# Temperature_Sensor_Rev_1.net
KiCad netlist of a schematic drawn in EAGLE
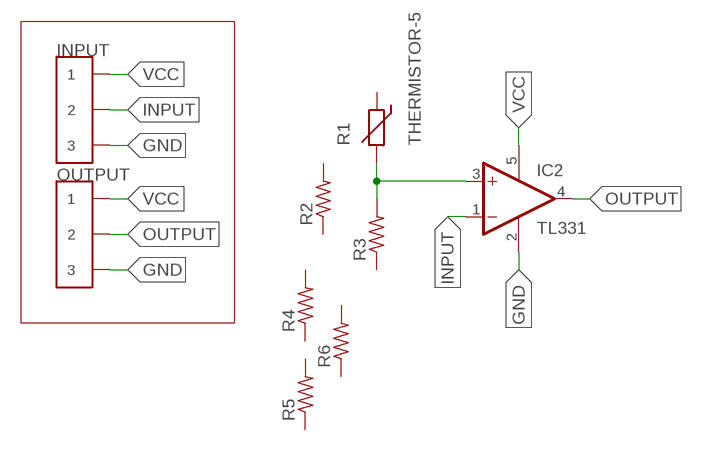
[diagram p0: schematic, sheet 1]

(export (version "E")
  (design (tool "Eeschema 10.0.6"))
  (components
    (comp (ref "IC2")
      (value "TL331")
      (footprint "eagle-import:DBV-R-PDSO-G5")
      (libsource (lib "eagle-import") (part "TL331"))
    )
    (comp (ref "INPUT")
      (value "CONN_3")
      (footprint "eagle-import:CONNECTOR_3")
      (libsource (lib "eagle-import") (part "CONN_3"))
    )
    (comp (ref "OUTPUT")
      (value "CONN_3")
      (footprint "eagle-import:CONNECTOR_3")
      (libsource (lib "eagle-import") (part "CONN_3"))
    )
    (comp (ref "R1")
      (value "THERMISTOR-5")
      (footprint "eagle-import:R-5")
      (libsource (lib "eagle-import") (part "THERMISTOR-5"))
    )
    (comp (ref "R2")
      (value "R-US_R0805")
      (footprint "eagle-import:R0805")
      (libsource (lib "eagle-import") (part "R-US_R0805"))
    )
    (comp (ref "R3")
      (value "R-US_R0805")
      (footprint "eagle-import:R0805")
      (libsource (lib "eagle-import") (part "R-US_R0805"))
    )
    (comp (ref "R4")
      (value "R-US_R0805")
      (footprint "eagle-import:R0805")
      (libsource (lib "eagle-import") (part "R-US_R0805"))
    )
    (comp (ref "R5")
      (value "R-US_R0805")
      (footprint "eagle-import:R0805")
      (libsource (lib "eagle-import") (part "R-US_R0805"))
    )
    (comp (ref "R6")
      (value "R-US_R0805")
      (footprint "eagle-import:R0805")
      (libsource (lib "eagle-import") (part "R-US_R0805"))
    )
  )
  (nets
    (net (code "1") (name "GND") (class "Default")
      (node (ref "IC2") (pin "2") (pinfunction "GND_2") (pintype "power_in"))
      (node (ref "INPUT") (pin "5") (pinfunction "3_5") (pintype "bidirectional"))
      (node (ref "INPUT") (pin "6") (pinfunction "3_6") (pintype "bidirectional"))
      (node (ref "OUTPUT") (pin "5") (pinfunction "3_5") (pintype "bidirectional"))
      (node (ref "OUTPUT") (pin "6") (pinfunction "3_6") (pintype "bidirectional"))
    )
    (net (code "2") (name "INPUT") (class "Default")
      (node (ref "IC2") (pin "1") (pinfunction "-IN_1") (pintype "input"))
      (node (ref "INPUT") (pin "3") (pinfunction "2_3") (pintype "bidirectional"))
      (node (ref "INPUT") (pin "4") (pinfunction "2_4") (pintype "bidirectional"))
    )
    (net (code "3") (name "Net-(IC2-+IN)") (class "Default")
      (node (ref "IC2") (pin "3") (pinfunction "+IN_3") (pintype "input"))
      (node (ref "R1") (pin "2") (pinfunction "2_2") (pintype "passive"))
      (node (ref "R3") (pin "2") (pinfunction "2_2") (pintype "passive"))
    )
    (net (code "4") (name "OUTPUT") (class "Default")
      (node (ref "IC2") (pin "4") (pinfunction "OUT_4") (pintype "output"))
      (node (ref "OUTPUT") (pin "3") (pinfunction "2_3") (pintype "bidirectional"))
      (node (ref "OUTPUT") (pin "4") (pinfunction "2_4") (pintype "bidirectional"))
    )
    (net (code "5") (name "VCC") (class "Default")
      (node (ref "IC2") (pin "5") (pinfunction "V+_5") (pintype "power_in"))
      (node (ref "INPUT") (pin "1") (pinfunction "1_1") (pintype "bidirectional"))
      (node (ref "INPUT") (pin "2") (pinfunction "1_2") (pintype "bidirectional"))
      (node (ref "OUTPUT") (pin "1") (pinfunction "1_1") (pintype "bidirectional"))
      (node (ref "OUTPUT") (pin "2") (pinfunction "1_2") (pintype "bidirectional"))
    )
    (net (code "6") (name "unconnected-(R1-Pad1)") (class "Default")
      (node (ref "R1") (pin "1") (pinfunction "1_1") (pintype "passive"))
    )
    (net (code "7") (name "unconnected-(R2-Pad1)") (class "Default")
      (node (ref "R2") (pin "1") (pinfunction "1_1") (pintype "passive"))
    )
    (net (code "8") (name "unconnected-(R2-Pad2)") (class "Default")
      (node (ref "R2") (pin "2") (pinfunction "2_2") (pintype "passive"))
    )
    (net (code "9") (name "unconnected-(R3-Pad1)") (class "Default")
      (node (ref "R3") (pin "1") (pinfunction "1_1") (pintype "passive"))
    )
    (net (code "10") (name "unconnected-(R4-Pad1)") (class "Default")
      (node (ref "R4") (pin "1") (pinfunction "1_1") (pintype "passive"))
    )
    (net (code "11") (name "unconnected-(R4-Pad2)") (class "Default")
      (node (ref "R4") (pin "2") (pinfunction "2_2") (pintype "passive"))
    )
    (net (code "12") (name "unconnected-(R5-Pad1)") (class "Default")
      (node (ref "R5") (pin "1") (pinfunction "1_1") (pintype "passive"))
    )
    (net (code "13") (name "unconnected-(R5-Pad2)") (class "Default")
      (node (ref "R5") (pin "2") (pinfunction "2_2") (pintype "passive"))
    )
    (net (code "14") (name "unconnected-(R6-Pad1)") (class "Default")
      (node (ref "R6") (pin "1") (pinfunction "1_1") (pintype "passive"))
    )
    (net (code "15") (name "unconnected-(R6-Pad2)") (class "Default")
      (node (ref "R6") (pin "2") (pinfunction "2_2") (pintype "passive"))
    )
  )
)
